# nixie-uhr-can.net
KiCad netlist of a schematic drawn in EAGLE
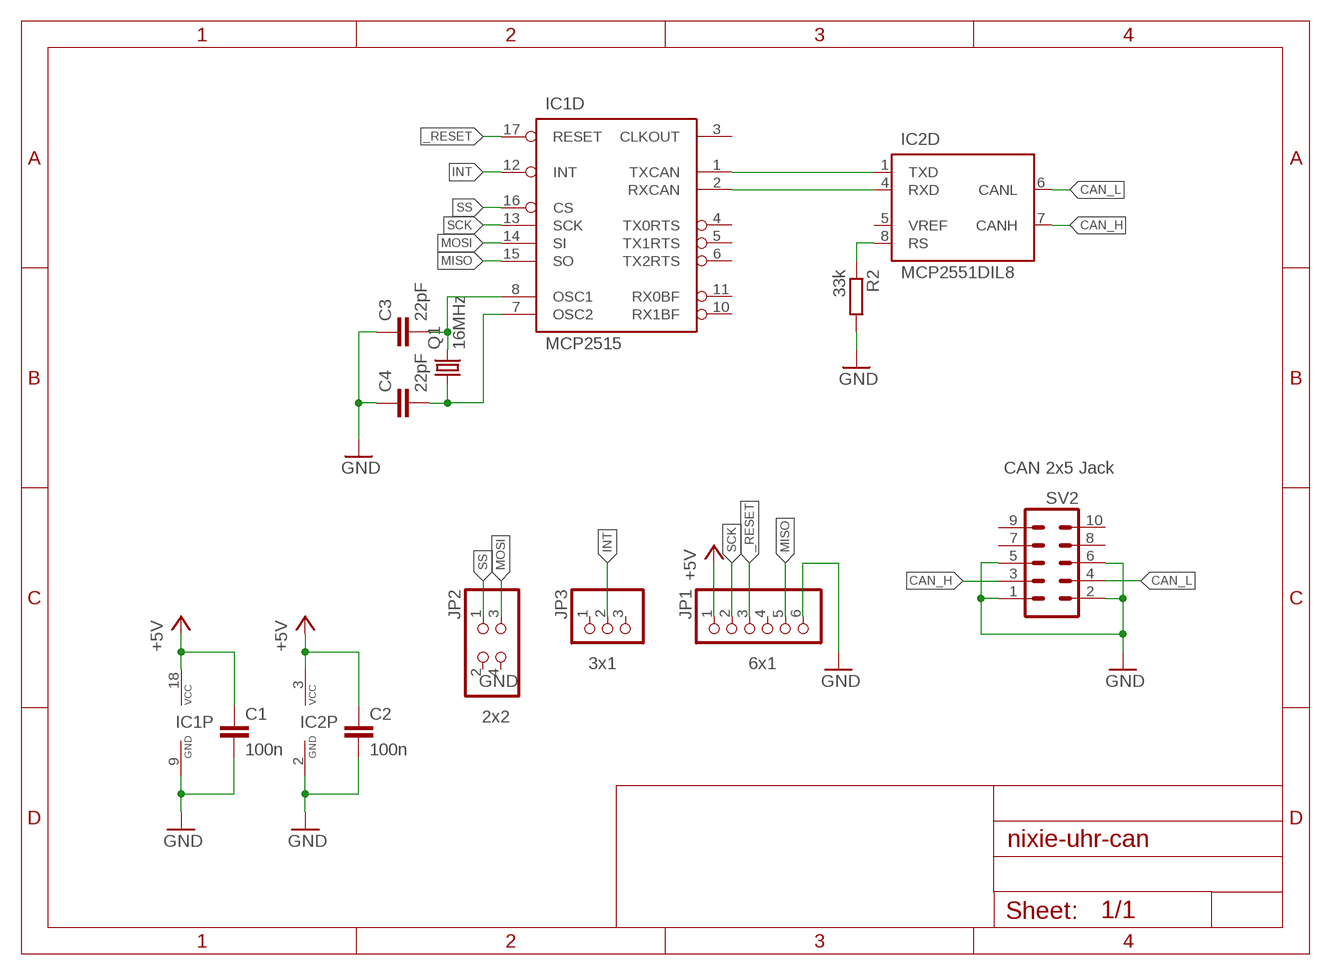
[diagram p0: schematic, sheet 1]

(export (version "E")
  (design (tool "Eeschema 10.0.6"))
  (components
    (comp (ref "C1")
      (value "100n")
      (footprint "eagle-import:C050-024X044")
      (libsource (lib "eagle-import") (part "C-EU050-024X044"))
    )
    (comp (ref "C2")
      (value "100n")
      (footprint "eagle-import:C050-024X044")
      (libsource (lib "eagle-import") (part "C-EU050-024X044"))
    )
    (comp (ref "C3")
      (value "22pF")
      (footprint "eagle-import:C0603")
      (libsource (lib "eagle-import") (part "resistor_C-EUC0603"))
    )
    (comp (ref "C4")
      (value "22pF")
      (footprint "eagle-import:C0603")
      (libsource (lib "eagle-import") (part "resistor_C-EUC0603"))
    )
    (comp (ref "IC1")
      (value "MCP2515")
      (footprint "eagle-import:DIL18")
      (libsource (lib "eagle-import") (part "MCP2515P"))
    )
    (comp (ref "IC2")
      (value "MCP2551DIL8")
      (footprint "eagle-import:DIL08")
      (libsource (lib "eagle-import") (part "MCP2551DIL8"))
    )
    (comp (ref "JP1")
      (value "6x1")
      (footprint "eagle-import:1X06_90")
      (libsource (lib "eagle-import") (part "PINHD-1X6/90"))
    )
    (comp (ref "JP2")
      (value "2x2")
      (footprint "eagle-import:2X02")
      (libsource (lib "eagle-import") (part "PINHD-2X2"))
    )
    (comp (ref "JP3")
      (value "3x1")
      (footprint "eagle-import:1X03")
      (libsource (lib "eagle-import") (part "PINHD-1X3"))
    )
    (comp (ref "Q1")
      (value "16MHz")
      (footprint "eagle-import:HC49UP")
      (libsource (lib "eagle-import") (part "CRYSTALHC49UP"))
    )
    (comp (ref "R2")
      (value "33k")
      (footprint "eagle-import:0204_7")
      (libsource (lib "eagle-import") (part "R-EU_0204/7"))
    )
    (comp (ref "SV2")
      (value "CAN 2x5 Jack")
      (footprint "eagle-import:ML10")
      (libsource (lib "eagle-import") (part "ML10"))
    )
  )
  (nets
    (net (code "1") (name "+5V") (class "Default")
      (node (ref "C1") (pin "1") (pinfunction "1_1") (pintype "passive"))
      (node (ref "C2") (pin "1") (pinfunction "1_1") (pintype "passive"))
      (node (ref "IC1") (pin "18") (pinfunction "VCC_18") (pintype "power_in"))
      (node (ref "IC2") (pin "3") (pinfunction "VCC_3") (pintype "power_in"))
      (node (ref "JP1") (pin "1") (pinfunction "1_1") (pintype "passive"))
    )
    (net (code "2") (name "CAN_H") (class "Default")
      (node (ref "IC2") (pin "7") (pinfunction "CANH_7") (pintype "bidirectional"))
      (node (ref "SV2") (pin "3") (pinfunction "3_3") (pintype "passive"))
    )
    (net (code "3") (name "CAN_L") (class "Default")
      (node (ref "IC2") (pin "6") (pinfunction "CANL_6") (pintype "bidirectional"))
      (node (ref "SV2") (pin "4") (pinfunction "4_4") (pintype "passive"))
    )
    (net (code "4") (name "GND") (class "Default")
      (node (ref "C1") (pin "2") (pinfunction "2_2") (pintype "passive"))
      (node (ref "C2") (pin "2") (pinfunction "2_2") (pintype "passive"))
      (node (ref "C3") (pin "1") (pinfunction "1_1") (pintype "passive"))
      (node (ref "C4") (pin "1") (pinfunction "1_1") (pintype "passive"))
      (node (ref "IC1") (pin "9") (pinfunction "GND_9") (pintype "power_in"))
      (node (ref "IC2") (pin "2") (pinfunction "GND_2") (pintype "power_in"))
      (node (ref "JP1") (pin "6") (pinfunction "6_6") (pintype "passive"))
      (node (ref "R2") (pin "2") (pinfunction "2_2") (pintype "passive"))
      (node (ref "SV2") (pin "1") (pinfunction "1_1") (pintype "passive"))
      (node (ref "SV2") (pin "2") (pinfunction "2_2") (pintype "passive"))
      (node (ref "SV2") (pin "5") (pinfunction "5_5") (pintype "passive"))
      (node (ref "SV2") (pin "6") (pinfunction "6_6") (pintype "passive"))
    )
    (net (code "5") (name "INT") (class "Default")
      (node (ref "IC1") (pin "12") (pinfunction "INT_12") (pintype "output"))
      (node (ref "JP3") (pin "2") (pinfunction "2_2") (pintype "passive"))
    )
    (net (code "6") (name "MISO") (class "Default")
      (node (ref "IC1") (pin "15") (pinfunction "SO_15") (pintype "output"))
      (node (ref "JP1") (pin "5") (pinfunction "5_5") (pintype "passive"))
    )
    (net (code "7") (name "MOSI") (class "Default")
      (node (ref "IC1") (pin "14") (pinfunction "SI_14") (pintype "input"))
      (node (ref "JP2") (pin "3") (pinfunction "3_3") (pintype "passive"))
    )
    (net (code "8") (name "Net-(IC1A-OSC1)") (class "Default")
      (node (ref "C3") (pin "2") (pinfunction "2_2") (pintype "passive"))
      (node (ref "IC1") (pin "8") (pinfunction "OSC1_8") (pintype "input"))
      (node (ref "Q1") (pin "2") (pinfunction "2_2") (pintype "passive"))
    )
    (net (code "9") (name "Net-(IC1A-OSC2)") (class "Default")
      (node (ref "C4") (pin "2") (pinfunction "2_2") (pintype "passive"))
      (node (ref "IC1") (pin "7") (pinfunction "OSC2_7") (pintype "input"))
      (node (ref "Q1") (pin "1") (pinfunction "1_1") (pintype "passive"))
    )
    (net (code "10") (name "Net-(IC1A-RXCAN)") (class "Default")
      (node (ref "IC1") (pin "2") (pinfunction "RXCAN_2") (pintype "input"))
      (node (ref "IC2") (pin "4") (pinfunction "RXD_4") (pintype "bidirectional"))
    )
    (net (code "11") (name "Net-(IC1A-TXCAN)") (class "Default")
      (node (ref "IC1") (pin "1") (pinfunction "TXCAN_1") (pintype "output"))
      (node (ref "IC2") (pin "1") (pinfunction "TXD_1") (pintype "bidirectional"))
    )
    (net (code "12") (name "Net-(IC2A-RS)") (class "Default")
      (node (ref "IC2") (pin "8") (pinfunction "RS_8") (pintype "bidirectional"))
      (node (ref "R2") (pin "1") (pinfunction "1_1") (pintype "passive"))
    )
    (net (code "13") (name "SCK") (class "Default")
      (node (ref "IC1") (pin "13") (pinfunction "SCK_13") (pintype "input"))
      (node (ref "JP1") (pin "2") (pinfunction "2_2") (pintype "passive"))
    )
    (net (code "14") (name "SS") (class "Default")
      (node (ref "IC1") (pin "16") (pinfunction "CS_16") (pintype "input"))
      (node (ref "JP2") (pin "1") (pinfunction "1_1") (pintype "passive"))
    )
    (net (code "15") (name "_RESET") (class "Default")
      (node (ref "IC1") (pin "17") (pinfunction "RESET_17") (pintype "input"))
      (node (ref "JP1") (pin "3") (pinfunction "3_3") (pintype "passive"))
    )
    (net (code "16") (name "unconnected-(IC1A-CLKOUT-Pad3)") (class "Default")
      (node (ref "IC1") (pin "3") (pinfunction "CLKOUT_3") (pintype "output"))
    )
    (net (code "17") (name "unconnected-(IC1A-RX0BF-Pad11)") (class "Default")
      (node (ref "IC1") (pin "11") (pinfunction "RX0BF_11") (pintype "output"))
    )
    (net (code "18") (name "unconnected-(IC1A-RX1BF-Pad10)") (class "Default")
      (node (ref "IC1") (pin "10") (pinfunction "RX1BF_10") (pintype "output"))
    )
    (net (code "19") (name "unconnected-(IC1A-TX0RTS-Pad4)") (class "Default")
      (node (ref "IC1") (pin "4") (pinfunction "TX0RTS_4") (pintype "input"))
    )
    (net (code "20") (name "unconnected-(IC1A-TX1RTS-Pad5)") (class "Default")
      (node (ref "IC1") (pin "5") (pinfunction "TX1RTS_5") (pintype "input"))
    )
    (net (code "21") (name "unconnected-(IC1A-TX2RTS-Pad6)") (class "Default")
      (node (ref "IC1") (pin "6") (pinfunction "TX2RTS_6") (pintype "input"))
    )
    (net (code "22") (name "unconnected-(IC2A-VREF-Pad5)") (class "Default")
      (node (ref "IC2") (pin "5") (pinfunction "VREF_5") (pintype "bidirectional"))
    )
    (net (code "23") (name "unconnected-(JP1-Pad4)") (class "Default")
      (node (ref "JP1") (pin "4") (pinfunction "4_4") (pintype "passive"))
    )
    (net (code "24") (name "unconnected-(JP2-Pad2)") (class "Default")
      (node (ref "JP2") (pin "2") (pinfunction "2_2") (pintype "passive"))
    )
    (net (code "25") (name "unconnected-(JP2-Pad4)") (class "Default")
      (node (ref "JP2") (pin "4") (pinfunction "4_4") (pintype "passive"))
    )
    (net (code "26") (name "unconnected-(JP3-Pad1)") (class "Default")
      (node (ref "JP3") (pin "1") (pinfunction "1_1") (pintype "passive"))
    )
    (net (code "27") (name "unconnected-(JP3-Pad3)") (class "Default")
      (node (ref "JP3") (pin "3") (pinfunction "3_3") (pintype "passive"))
    )
    (net (code "28") (name "unconnected-(SV2-Pad7)") (class "Default")
      (node (ref "SV2") (pin "7") (pinfunction "7_7") (pintype "passive"))
    )
    (net (code "29") (name "unconnected-(SV2-Pad8)") (class "Default")
      (node (ref "SV2") (pin "8") (pinfunction "8_8") (pintype "passive"))
    )
    (net (code "30") (name "unconnected-(SV2-Pad9)") (class "Default")
      (node (ref "SV2") (pin "9") (pinfunction "9_9") (pintype "passive"))
    )
    (net (code "31") (name "unconnected-(SV2-Pad10)") (class "Default")
      (node (ref "SV2") (pin "10") (pinfunction "10_10") (pintype "passive"))
    )
  )
)
